# USB.net
KiCad netlist of a schematic drawn in Altium Designer
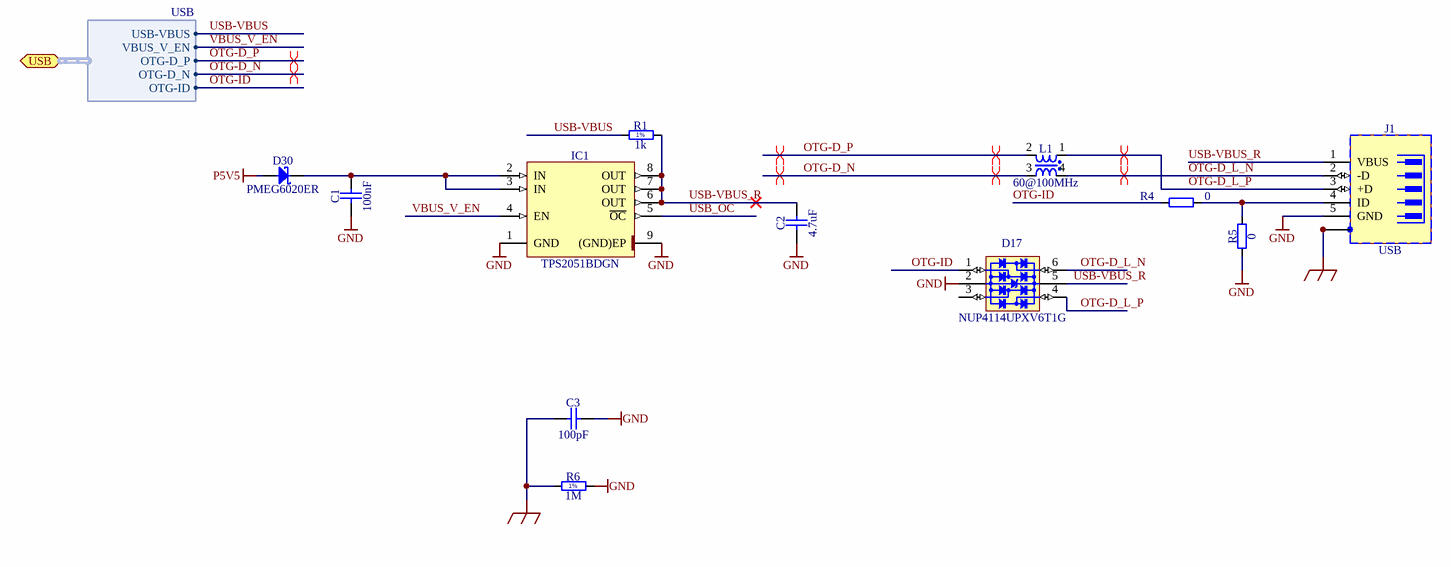
[diagram p0: USB.SchDoc]

(export (version "E")
  (design (tool "Eeschema 10.0.6"))
  (components
    (comp (ref "C1")
      (value "100nF")
      (footprint "CAPC1005X55N")
      (description "Non-polarised capacitor")
      (fields
        (field (name "PART NUMBER") "CC0402_100NF_16V_10%_X5R")
        (field (name "VOLTAGE") "16V")
        (field (name "AUTHOR") "CERN DEM JLC")
      )
      (libsource (lib "Capacitors") (part "Capacitor - non polarized"))
    )
    (comp (ref "C2")
      (value "4.7uF")
      (footprint "CAPC1709X95N")
      (description "Non-polarised capacitor")
      (fields
        (field (name "PART NUMBER") "CC0603_4.7UF_16V_10%_X5R")
        (field (name "VOLTAGE") "16V")
        (field (name "AUTHOR") "CERN DEM JLC")
      )
      (libsource (lib "Capacitors") (part "Capacitor - non polarized"))
    )
    (comp (ref "C3")
      (value "100pF")
      (footprint "CAPC3216X180N")
      (description "Non-polarised capacitor")
      (fields
        (field (name "PART NUMBER") "CC1206_100PF_2KV_5%_C0G")
        (field (name "VOLTAGE") "2kV")
        (field (name "AUTHOR") "CERN DEM JLC")
      )
      (libsource (lib "Capacitors") (part "Capacitor - non polarized"))
    )
    (comp (ref "D17")
      (value "NUP4114UPXV6T1G")
      (footprint "SOTFL50P160X60-6N")
      (fields
        (field (name "VOLTAGE") "5.5V")
        (field (name "MANUFACTURER") "ON SEMICONDUCTOR")
        (field (name "AUTHOR") "CERN DEM JLC")
      )
      (libsource (lib "ICs And Semiconductors") (part "NUP4114"))
    )
    (comp (ref "D30")
      (value "PMEG6020ER")
      (footprint "SODFL3517X110N")
      (description "Schottky Diode")
      (fields
        (field (name "VOLTAGE") "60V")
        (field (name "POWER") "2A")
        (field (name "AUTHOR") "CERN DEM JMW")
      )
      (libsource (lib "ICs And Semiconductors") (part "Diode Schottky"))
    )
    (comp (ref "IC1")
      (value "TPS2051BDGN")
      (footprint "SOP65P490X110-9N-R157X189")
      (description "One Channel, Current-Limited, Power-Distribution Switches")
      (fields (field (name "MANUFACTURER") "TEXAS INSTRUMENTS") (field (name "AUTHOR") "CERN DEM BC"))
      (libsource (lib "ICs And Semiconductors") (part "TPS2051BDGN"))
    )
    (comp (ref "J1")
      (value "USB")
      (footprint "UJ2-MIBH-4-MSMT")
      (description "5 Pin + 1 Shield  in-line USB Receptacle")
      (fields
        (field (name "PART NUMBER") "CUI_UJ2-MIBH-4-MSMT")
        (field (name "MANUFACTURER") "CUI")
        (field (name "AUTHOR") "GK")
      )
      (libsource (lib "Stabilizer") (part "CON_USB_UJ2-MIBH-4-MSMT"))
    )
    (comp (ref "L1")
      (value "60@100MHz")
      (footprint "IND_WURTH_WE-CNSW_0504")
      (description "Inductor Common Mode")
      (fields
        (field (name "PART NUMBER") "IND0504_WURTH_7442335600")
        (field (name "POWER") "600mA")
        (field (name "AUTHOR") "CERN DEM BC")
      )
      (libsource (lib "Inductors & Transformers") (part "Inductor Common Mode 1Dot-2 4Dot-3"))
    )
    (comp (ref "R1")
      (value "1k")
      (footprint "RESC1005X40N")
      (description "Resistor - 1%")
      (fields
        (field (name "PART NUMBER") "R0402_1K_1%_0.0625W_100PPM")
        (field (name "MANUFACTURER") "GENERIC")
        (field (name "AUTHOR") "CERN DEM JLC")
      )
      (libsource (lib "Resistors") (part "Resistor - 1%"))
    )
    (comp (ref "R4")
      (value "0")
      (footprint "RESC1005X40N")
      (description "Resistor")
      (fields
        (field (name "PART NUMBER") "R0402_0R_JUMPER")
        (field (name "MANUFACTURER") "GENERIC")
        (field (name "AUTHOR") "CERN DEM JLC")
      )
      (libsource (lib "Resistors") (part "Resistor"))
    )
    (comp (ref "R5")
      (value "0")
      (footprint "RESC1005X40N")
      (description "Resistor")
      (fields
        (field (name "PART NUMBER") "R0402_0R_JUMPER")
        (field (name "MANUFACTURER") "GENERIC")
        (field (name "AUTHOR") "CERN DEM JLC")
      )
      (libsource (lib "Resistors") (part "Resistor"))
    )
    (comp (ref "R6")
      (value "1M")
      (footprint "RESC1005X40N")
      (description "Resistor - 1%")
      (fields
        (field (name "PART NUMBER") "R0402_1M_1%_0.0625W_100PPM")
        (field (name "MANUFACTURER") "GENERIC")
        (field (name "AUTHOR") "CERN DEM JLC")
      )
      (libsource (lib "Resistors") (part "Resistor - 1%"))
    )
  )
  (nets
    (net (code "2") (name "/OTG-D_L_N") (class "Default")
      (node (ref "D17") (pin "6") (pinfunction "I/O4_6") (pintype "bidirectional"))
      (node (ref "J1") (pin "2") (pinfunction "-D_2") (pintype "bidirectional"))
      (node (ref "L1") (pin "4") (pinfunction "4_4") (pintype "passive"))
    )
    (net (code "3") (name "/OTG-D_L_P") (class "Default")
      (node (ref "D17") (pin "4") (pinfunction "I/O3_4") (pintype "bidirectional"))
      (node (ref "J1") (pin "3") (pinfunction "+D_3") (pintype "bidirectional"))
      (node (ref "L1") (pin "1") (pinfunction "1_1") (pintype "passive"))
    )
    (net (code "4") (name "/OTG-D_N") (class "Default")
      (node (ref "L1") (pin "3") (pinfunction "3_3") (pintype "passive"))
    )
    (net (code "5") (name "/OTG-D_P") (class "Default")
      (node (ref "L1") (pin "2") (pinfunction "2_2") (pintype "passive"))
    )
    (net (code "6") (name "/OTG-ID") (class "Default")
      (node (ref "D17") (pin "1") (pinfunction "I/O1_1") (pintype "bidirectional"))
      (node (ref "R4") (pin "1") (pinfunction "1_1") (pintype "passive"))
    )
    (net (code "7") (name "/USB-VBUS") (class "Default")
      (node (ref "R1") (pin "1") (pinfunction "1_1") (pintype "passive"))
    )
    (net (code "8") (name "/USB-VBUS_R") (class "Default")
      (node (ref "C2") (pin "2") (pinfunction "2_2") (pintype "passive"))
      (node (ref "D17") (pin "5") (pinfunction "VBUS_5") (pintype "power_in"))
      (node (ref "IC1") (pin "6") (pinfunction "OUT_6") (pintype "output"))
      (node (ref "IC1") (pin "7") (pinfunction "OUT_7") (pintype "output"))
      (node (ref "IC1") (pin "8") (pinfunction "OUT_8") (pintype "output"))
      (node (ref "J1") (pin "1") (pinfunction "VBUS_1") (pintype "power_in"))
      (node (ref "R1") (pin "2") (pinfunction "2_2") (pintype "passive"))
    )
    (net (code "9") (name "/USB_OC") (class "Default")
      (node (ref "IC1") (pin "5") (pinfunction "~{OC}_5") (pintype "output"))
    )
    (net (code "10") (name "/VBUS_V_EN") (class "Default")
      (node (ref "IC1") (pin "4") (pinfunction "EN_4") (pintype "input"))
    )
    (net (code "12") (name "FGND") (class "Default")
      (node (ref "C3") (pin "1") (pinfunction "1_1") (pintype "passive"))
      (node (ref "J1") (pin "10") (pinfunction "SH_10") (pintype "power_in"))
      (node (ref "J1") (pin "11") (pinfunction "SH_11") (pintype "power_in"))
      (node (ref "J1") (pin "6") (pinfunction "SH_6") (pintype "power_in"))
      (node (ref "J1") (pin "7") (pinfunction "SH_7") (pintype "power_in"))
      (node (ref "J1") (pin "8") (pinfunction "SH_8") (pintype "power_in"))
      (node (ref "J1") (pin "9") (pinfunction "SH_9") (pintype "power_in"))
      (node (ref "R6") (pin "1") (pinfunction "1_1") (pintype "passive"))
    )
    (net (code "13") (name "GND") (class "Default")
      (node (ref "C1") (pin "1") (pinfunction "1_1") (pintype "passive"))
      (node (ref "C2") (pin "1") (pinfunction "1_1") (pintype "passive"))
      (node (ref "C3") (pin "2") (pinfunction "2_2") (pintype "passive"))
      (node (ref "D17") (pin "2") (pinfunction "GND_2") (pintype "power_in"))
      (node (ref "IC1") (pin "1") (pinfunction "GND_1") (pintype "power_in"))
      (node (ref "IC1") (pin "9") (pinfunction "(GND)EP_9") (pintype "power_in"))
      (node (ref "J1") (pin "5") (pinfunction "GND_5") (pintype "power_in"))
      (node (ref "R5") (pin "1") (pinfunction "1_1") (pintype "passive"))
      (node (ref "R6") (pin "2") (pinfunction "2_2") (pintype "passive"))
    )
    (net (code "14") (name "Net-(D30-C)") (class "Default")
      (node (ref "C1") (pin "2") (pinfunction "2_2") (pintype "passive"))
      (node (ref "D30") (pin "1") (pinfunction "C_1") (pintype "passive"))
      (node (ref "IC1") (pin "2") (pinfunction "IN_2") (pintype "input"))
      (node (ref "IC1") (pin "3") (pinfunction "IN_3") (pintype "input"))
    )
    (net (code "15") (name "Net-(J1-ID)") (class "Default")
      (node (ref "J1") (pin "4") (pinfunction "ID_4") (pintype "passive"))
      (node (ref "R4") (pin "2") (pinfunction "2_2") (pintype "passive"))
      (node (ref "R5") (pin "2") (pinfunction "2_2") (pintype "passive"))
    )
    (net (code "16") (name "P5V5") (class "Default")
      (node (ref "D30") (pin "2") (pinfunction "A_2") (pintype "passive"))
    )
    (net (code "17") (name "unconnected-(D17-I{slash}O2-Pad3)") (class "Default")
      (node (ref "D17") (pin "3") (pinfunction "I/O2_3") (pintype "bidirectional"))
    )
  )
)
